# piezo_flasher_v1_1.net
KiCad netlist of a schematic drawn in EAGLE
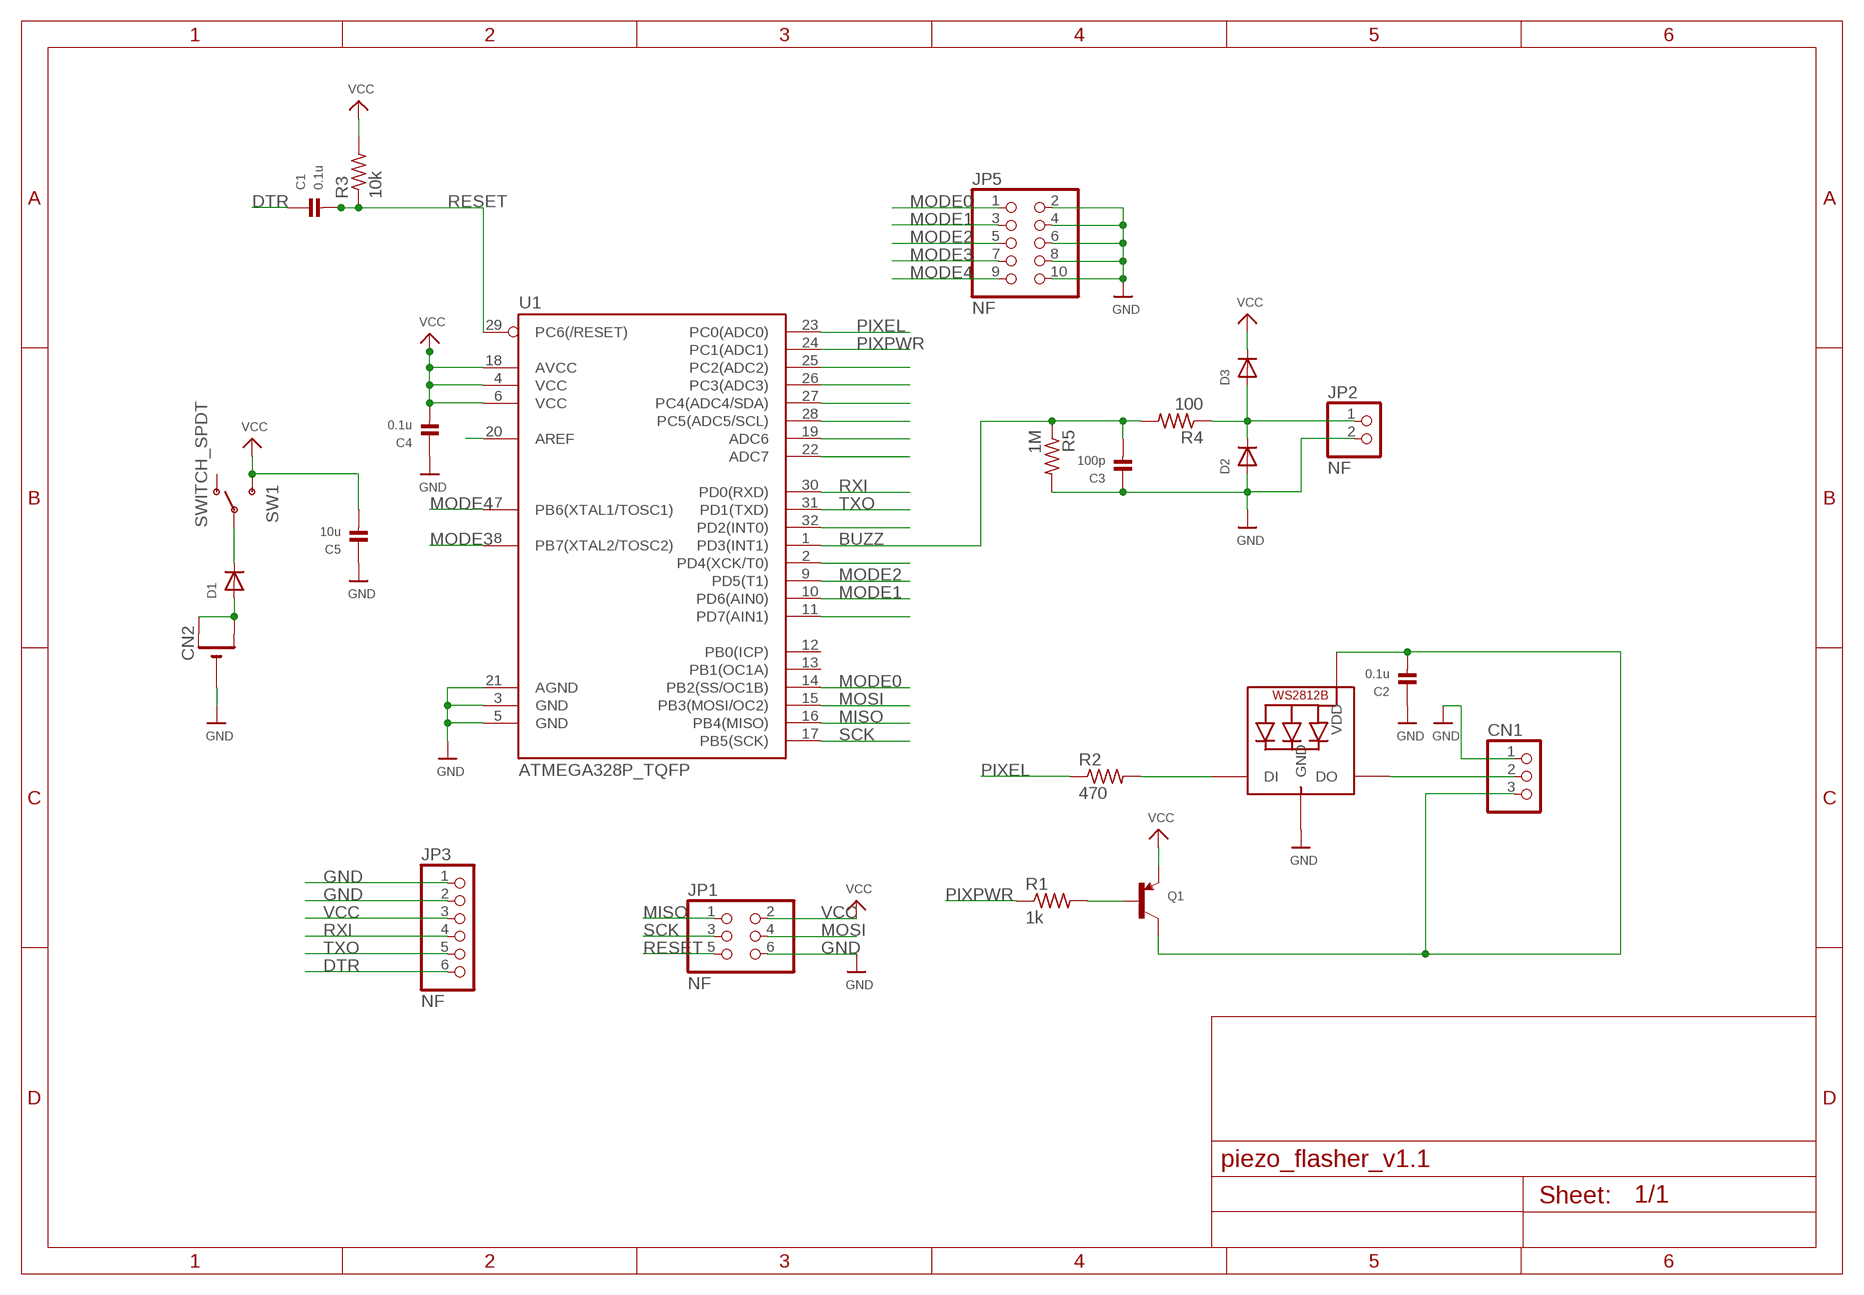
[diagram p0: schematic, sheet 1]

(export (version "E")
  (design (tool "Eeschema 10.0.6"))
  (components
    (comp (ref "C1")
      (value "0.1u")
      (footprint "eagle-import:0805")
      (libsource (lib "eagle-import") (part "CAP_CERAMIC0805"))
    )
    (comp (ref "C2")
      (value "0.1u")
      (footprint "eagle-import:0805")
      (libsource (lib "eagle-import") (part "CAP_CERAMIC0805"))
    )
    (comp (ref "C3")
      (value "100p")
      (footprint "eagle-import:0805")
      (libsource (lib "eagle-import") (part "CAP_CERAMIC0805"))
    )
    (comp (ref "C4")
      (value "0.1u")
      (footprint "eagle-import:0805")
      (libsource (lib "eagle-import") (part "CAP_CERAMIC0805"))
    )
    (comp (ref "C5")
      (value "10u")
      (footprint "eagle-import:0805")
      (libsource (lib "eagle-import") (part "CAP_CERAMIC0805"))
    )
    (comp (ref "CN1")
      (value "JST_3PIN")
      (footprint "eagle-import:JSTPH3")
      (libsource (lib "eagle-import") (part "JST_3PIN"))
    )
    (comp (ref "CN2")
      (value "CR2032SMT")
      (footprint "eagle-import:CR2032-SMD")
      (libsource (lib "eagle-import") (part "CR2032SMT"))
    )
    (comp (ref "D1")
      (value "DIODESOD-323")
      (footprint "eagle-import:SOD-323")
      (libsource (lib "eagle-import") (part "DIODESOD-323"))
    )
    (comp (ref "D2")
      (value "DIODESOD-323")
      (footprint "eagle-import:SOD-323")
      (libsource (lib "eagle-import") (part "DIODESOD-323"))
    )
    (comp (ref "D3")
      (value "DIODESOD-323")
      (footprint "eagle-import:SOD-323")
      (libsource (lib "eagle-import") (part "DIODESOD-323"))
    )
    (comp (ref "JP1")
      (value "NF")
      (footprint "eagle-import:2X03_ROUND_70MIL")
      (libsource (lib "eagle-import") (part "HEADER-2X3"))
    )
    (comp (ref "JP2")
      (value "NF")
      (footprint "eagle-import:1X02_ROUND")
      (libsource (lib "eagle-import") (part "HEADER-1X2ROUND"))
    )
    (comp (ref "JP3")
      (value "NF")
      (footprint "eagle-import:1X06_ROUND")
      (libsource (lib "eagle-import") (part "HEADER-1X6ROUND"))
    )
    (comp (ref "JP5")
      (value "NF")
      (footprint "eagle-import:2X05")
      (libsource (lib "eagle-import") (part "HEADER-2X5"))
    )
    (comp (ref "LED1")
      (value "WS2812B5050")
      (footprint "eagle-import:WS2812B")
      (libsource (lib "eagle-import") (part "WS2812B5050"))
    )
    (comp (ref "Q1")
      (value "TRANSISTOR_PNPWIDE")
      (footprint "eagle-import:SOT23-WIDE")
      (libsource (lib "eagle-import") (part "TRANSISTOR_PNPWIDE"))
    )
    (comp (ref "R1")
      (value "1k")
      (footprint "eagle-import:R0805")
      (libsource (lib "eagle-import") (part "R-US_R0805"))
    )
    (comp (ref "R2")
      (value "470")
      (footprint "eagle-import:R0805")
      (libsource (lib "eagle-import") (part "R-US_R0805"))
    )
    (comp (ref "R3")
      (value "10k")
      (footprint "eagle-import:R0805")
      (libsource (lib "eagle-import") (part "R-US_R0805"))
    )
    (comp (ref "R4")
      (value "100")
      (footprint "eagle-import:R0805")
      (libsource (lib "eagle-import") (part "R-US_R0805"))
    )
    (comp (ref "R5")
      (value "1M")
      (footprint "eagle-import:R0805")
      (libsource (lib "eagle-import") (part "R-US_R0805"))
    )
    (comp (ref "SW1")
      (value "SWITCH_SPDT")
      (footprint "eagle-import:KPS-1290")
      (libsource (lib "eagle-import") (part "SWITCH_SPDT"))
    )
    (comp (ref "U1")
      (value "ATMEGA328P_TQFP")
      (footprint "eagle-import:TQFP32-08")
      (libsource (lib "eagle-import") (part "ATMEGA328P_TQFP"))
    )
  )
  (nets
    (net (code "1") (name "/BUZZ") (class "Default")
      (node (ref "C3") (pin "2") (pinfunction "P$2_2") (pintype "passive"))
      (node (ref "R4") (pin "2") (pinfunction "2_2") (pintype "passive"))
      (node (ref "R5") (pin "1") (pinfunction "1_1") (pintype "passive"))
      (node (ref "U1") (pin "1") (pinfunction "PD3(INT1)_1") (pintype "bidirectional"))
    )
    (net (code "2") (name "/DTR") (class "Default")
      (node (ref "C1") (pin "1") (pinfunction "P$1_1") (pintype "passive"))
      (node (ref "JP3") (pin "6") (pinfunction "6_6") (pintype "passive"))
    )
    (net (code "3") (name "/MISO") (class "Default")
      (node (ref "JP1") (pin "1") (pinfunction "1_1") (pintype "passive"))
      (node (ref "U1") (pin "16") (pinfunction "PB4(MISO)_16") (pintype "bidirectional"))
    )
    (net (code "4") (name "/MODE0") (class "Default")
      (node (ref "JP5") (pin "1") (pinfunction "1_1") (pintype "passive"))
      (node (ref "U1") (pin "14") (pinfunction "PB2(SS/OC1B)_14") (pintype "bidirectional"))
    )
    (net (code "5") (name "/MODE1") (class "Default")
      (node (ref "JP5") (pin "3") (pinfunction "3_3") (pintype "passive"))
      (node (ref "U1") (pin "10") (pinfunction "PD6(AIN0)_10") (pintype "bidirectional"))
    )
    (net (code "6") (name "/MODE2") (class "Default")
      (node (ref "JP5") (pin "5") (pinfunction "5_5") (pintype "passive"))
      (node (ref "U1") (pin "9") (pinfunction "PD5(T1)_9") (pintype "bidirectional"))
    )
    (net (code "7") (name "/MODE3") (class "Default")
      (node (ref "JP5") (pin "7") (pinfunction "7_7") (pintype "passive"))
      (node (ref "U1") (pin "8") (pinfunction "PB7(XTAL2/TOSC2)_8") (pintype "bidirectional"))
    )
    (net (code "8") (name "/MODE4") (class "Default")
      (node (ref "JP5") (pin "9") (pinfunction "9_9") (pintype "passive"))
      (node (ref "U1") (pin "7") (pinfunction "PB6(XTAL1/TOSC1)_7") (pintype "bidirectional"))
    )
    (net (code "9") (name "/MOSI") (class "Default")
      (node (ref "JP1") (pin "4") (pinfunction "4_4") (pintype "passive"))
      (node (ref "U1") (pin "15") (pinfunction "PB3(MOSI/OC2)_15") (pintype "bidirectional"))
    )
    (net (code "10") (name "/PIXEL") (class "Default")
      (node (ref "R2") (pin "1") (pinfunction "1_1") (pintype "passive"))
      (node (ref "U1") (pin "23") (pinfunction "PC0(ADC0)_23") (pintype "bidirectional"))
    )
    (net (code "11") (name "/PIXPWR") (class "Default")
      (node (ref "R1") (pin "1") (pinfunction "1_1") (pintype "passive"))
      (node (ref "U1") (pin "24") (pinfunction "PC1(ADC1)_24") (pintype "bidirectional"))
    )
    (net (code "12") (name "/RESET") (class "Default")
      (node (ref "C1") (pin "2") (pinfunction "P$2_2") (pintype "passive"))
      (node (ref "JP1") (pin "5") (pinfunction "5_5") (pintype "passive"))
      (node (ref "R3") (pin "1") (pinfunction "1_1") (pintype "passive"))
      (node (ref "U1") (pin "29") (pinfunction "PC6(/RESET)_29") (pintype "bidirectional"))
    )
    (net (code "13") (name "/RXI") (class "Default")
      (node (ref "JP3") (pin "4") (pinfunction "4_4") (pintype "passive"))
      (node (ref "U1") (pin "30") (pinfunction "PD0(RXD)_30") (pintype "bidirectional"))
    )
    (net (code "14") (name "/SCK") (class "Default")
      (node (ref "JP1") (pin "3") (pinfunction "3_3") (pintype "passive"))
      (node (ref "U1") (pin "17") (pinfunction "PB5(SCK)_17") (pintype "bidirectional"))
    )
    (net (code "15") (name "/TXO") (class "Default")
      (node (ref "JP3") (pin "5") (pinfunction "5_5") (pintype "passive"))
      (node (ref "U1") (pin "31") (pinfunction "PD1(TXD)_31") (pintype "bidirectional"))
    )
    (net (code "16") (name "GND") (class "Default")
      (node (ref "C2") (pin "1") (pinfunction "P$1_1") (pintype "passive"))
      (node (ref "C3") (pin "1") (pinfunction "P$1_1") (pintype "passive"))
      (node (ref "C4") (pin "1") (pinfunction "P$1_1") (pintype "passive"))
      (node (ref "C5") (pin "1") (pinfunction "P$1_1") (pintype "passive"))
      (node (ref "CN1") (pin "1") (pinfunction "1_1") (pintype "passive"))
      (node (ref "CN2") (pin "-") (pinfunction "-_-") (pintype "passive"))
      (node (ref "D2") (pin "A") (pinfunction "A_A") (pintype "passive"))
      (node (ref "JP1") (pin "6") (pinfunction "6_6") (pintype "passive"))
      (node (ref "JP2") (pin "2") (pinfunction "2_2") (pintype "passive"))
      (node (ref "JP3") (pin "1") (pinfunction "1_1") (pintype "passive"))
      (node (ref "JP3") (pin "2") (pinfunction "2_2") (pintype "passive"))
      (node (ref "JP5") (pin "10") (pinfunction "10_10") (pintype "passive"))
      (node (ref "JP5") (pin "2") (pinfunction "2_2") (pintype "passive"))
      (node (ref "JP5") (pin "4") (pinfunction "4_4") (pintype "passive"))
      (node (ref "JP5") (pin "6") (pinfunction "6_6") (pintype "passive"))
      (node (ref "JP5") (pin "8") (pinfunction "8_8") (pintype "passive"))
      (node (ref "LED1") (pin "3-GND") (pinfunction "GND_3-GND") (pintype "power_in"))
      (node (ref "R5") (pin "2") (pinfunction "2_2") (pintype "passive"))
      (node (ref "U1") (pin "21") (pinfunction "AGND_21") (pintype "bidirectional"))
      (node (ref "U1") (pin "3") (pinfunction "GND_3") (pintype "bidirectional"))
      (node (ref "U1") (pin "5") (pinfunction "GND_5") (pintype "bidirectional"))
    )
    (net (code "17") (name "Net-(C2-P$2)") (class "Default")
      (node (ref "C2") (pin "2") (pinfunction "P$2_2") (pintype "passive"))
      (node (ref "CN1") (pin "3") (pinfunction "3_3") (pintype "passive"))
      (node (ref "LED1") (pin "1-VDD") (pinfunction "VDD_1-VDD") (pintype "power_in"))
      (node (ref "Q1") (pin "3") (pinfunction "C_3") (pintype "passive"))
    )
    (net (code "18") (name "Net-(CN2-+)") (class "Default")
      (node (ref "CN2") (pin "+$1") (pinfunction "+_+$1") (pintype "passive"))
      (node (ref "CN2") (pin "+$2") (pinfunction "+1_+$2") (pintype "passive"))
      (node (ref "D1") (pin "A") (pinfunction "A_A") (pintype "passive"))
    )
    (net (code "19") (name "Net-(D1-PadC)") (class "Default")
      (node (ref "D1") (pin "C") (pinfunction "C_C") (pintype "passive"))
      (node (ref "SW1") (pin "P") (pinfunction "P_P") (pintype "passive"))
    )
    (net (code "20") (name "Net-(D2-PadC)") (class "Default")
      (node (ref "D2") (pin "C") (pinfunction "C_C") (pintype "passive"))
      (node (ref "D3") (pin "A") (pinfunction "A_A") (pintype "passive"))
      (node (ref "JP2") (pin "1") (pinfunction "1_1") (pintype "passive"))
      (node (ref "R4") (pin "1") (pinfunction "1_1") (pintype "passive"))
    )
    (net (code "21") (name "Net-(LED1-DI)") (class "Default")
      (node (ref "LED1") (pin "4-DIN") (pinfunction "DI_4-DIN") (pintype "input"))
      (node (ref "R2") (pin "2") (pinfunction "2_2") (pintype "passive"))
    )
    (net (code "22") (name "Net-(LED1-DO)") (class "Default")
      (node (ref "CN1") (pin "2") (pinfunction "2_2") (pintype "passive"))
      (node (ref "LED1") (pin "2-DOUT") (pinfunction "DO_2-DOUT") (pintype "output"))
    )
    (net (code "23") (name "Net-(Q1-B)") (class "Default")
      (node (ref "Q1") (pin "1") (pinfunction "B_1") (pintype "passive"))
      (node (ref "R1") (pin "2") (pinfunction "2_2") (pintype "passive"))
    )
    (net (code "24") (name "VCC") (class "Default")
      (node (ref "C4") (pin "2") (pinfunction "P$2_2") (pintype "passive"))
      (node (ref "C5") (pin "2") (pinfunction "P$2_2") (pintype "passive"))
      (node (ref "D3") (pin "C") (pinfunction "C_C") (pintype "passive"))
      (node (ref "JP1") (pin "2") (pinfunction "2_2") (pintype "passive"))
      (node (ref "JP3") (pin "3") (pinfunction "3_3") (pintype "passive"))
      (node (ref "Q1") (pin "2") (pinfunction "E_2") (pintype "passive"))
      (node (ref "R3") (pin "2") (pinfunction "2_2") (pintype "passive"))
      (node (ref "SW1") (pin "S") (pinfunction "S_S") (pintype "passive"))
      (node (ref "U1") (pin "18") (pinfunction "AVCC_18") (pintype "bidirectional"))
      (node (ref "U1") (pin "4") (pinfunction "VCC_4") (pintype "bidirectional"))
      (node (ref "U1") (pin "6") (pinfunction "VCC_6") (pintype "bidirectional"))
    )
    (net (code "25") (name "unconnected-(SW1-PadO)") (class "Default")
      (node (ref "SW1") (pin "O") (pinfunction "O_O") (pintype "passive"))
    )
    (net (code "26") (name "unconnected-(U1-ADC6-Pad19)") (class "Default")
      (node (ref "U1") (pin "19") (pinfunction "ADC6_19") (pintype "bidirectional"))
    )
    (net (code "27") (name "unconnected-(U1-ADC7-Pad22)") (class "Default")
      (node (ref "U1") (pin "22") (pinfunction "ADC7_22") (pintype "bidirectional"))
    )
    (net (code "28") (name "unconnected-(U1-AREF-Pad20)") (class "Default")
      (node (ref "U1") (pin "20") (pinfunction "AREF_20") (pintype "bidirectional"))
    )
    (net (code "29") (name "unconnected-(U1-PB0(ICP)-Pad12)") (class "Default")
      (node (ref "U1") (pin "12") (pinfunction "PB0(ICP)_12") (pintype "bidirectional"))
    )
    (net (code "30") (name "unconnected-(U1-PB1(OC1A)-Pad13)") (class "Default")
      (node (ref "U1") (pin "13") (pinfunction "PB1(OC1A)_13") (pintype "bidirectional"))
    )
    (net (code "31") (name "unconnected-(U1-PC2(ADC2)-Pad25)") (class "Default")
      (node (ref "U1") (pin "25") (pinfunction "PC2(ADC2)_25") (pintype "bidirectional"))
    )
    (net (code "32") (name "unconnected-(U1-PC3(ADC3)-Pad26)") (class "Default")
      (node (ref "U1") (pin "26") (pinfunction "PC3(ADC3)_26") (pintype "bidirectional"))
    )
    (net (code "33") (name "unconnected-(U1-PC4(ADC4{slash}SDA)-Pad27)") (class "Default")
      (node (ref "U1") (pin "27") (pinfunction "PC4(ADC4/SDA)_27") (pintype "bidirectional"))
    )
    (net (code "34") (name "unconnected-(U1-PC5(ADC5{slash}SCL)-Pad28)") (class "Default")
      (node (ref "U1") (pin "28") (pinfunction "PC5(ADC5/SCL)_28") (pintype "bidirectional"))
    )
    (net (code "35") (name "unconnected-(U1-PD2(INT0)-Pad32)") (class "Default")
      (node (ref "U1") (pin "32") (pinfunction "PD2(INT0)_32") (pintype "bidirectional"))
    )
    (net (code "36") (name "unconnected-(U1-PD4(XCK{slash}T0)-Pad2)") (class "Default")
      (node (ref "U1") (pin "2") (pinfunction "PD4(XCK/T0)_2") (pintype "bidirectional"))
    )
    (net (code "37") (name "unconnected-(U1-PD7(AIN1)-Pad11)") (class "Default")
      (node (ref "U1") (pin "11") (pinfunction "PD7(AIN1)_11") (pintype "bidirectional"))
    )
  )
)
